# power-supply.net
KiCad netlist of a schematic drawn in EAGLE
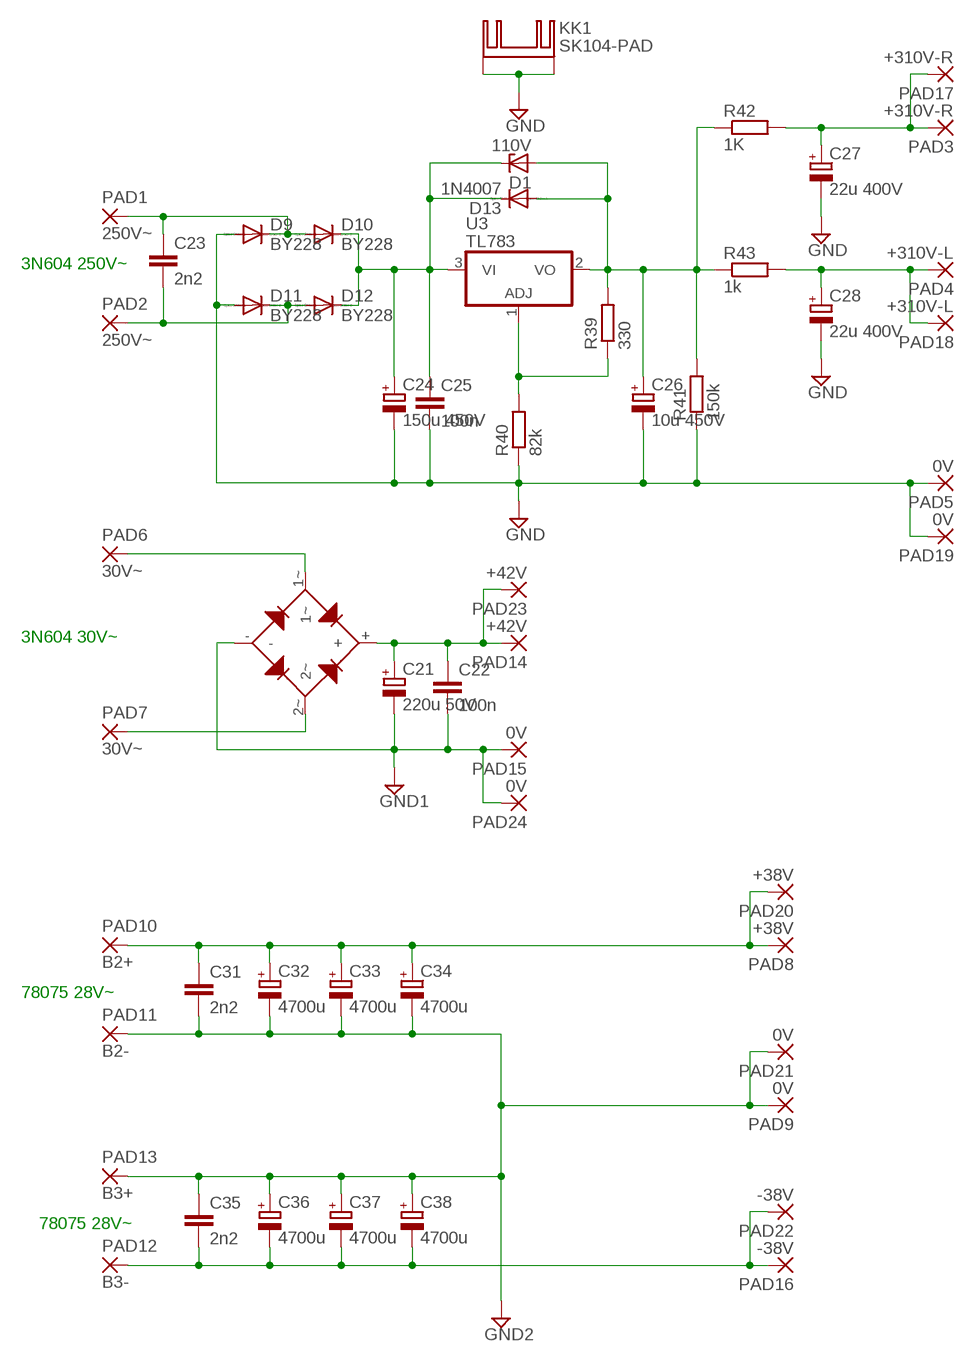
[diagram p0: schematic, sheet 1]

(export (version "E")
  (design (tool "Eeschema 10.0.6"))
  (components
    (comp (ref "C21")
      (value "220u 50V")
      (footprint "eagle-import:E5-10,5")
      (libsource (lib "eagle-import") (part "CPOL-EUE5-10.5"))
    )
    (comp (ref "C22")
      (value "100n")
      (footprint "eagle-import:C050-025X075")
      (libsource (lib "eagle-import") (part "C-EU050-025X075"))
    )
    (comp (ref "C23")
      (value "2n2")
      (footprint "eagle-import:C225-087X268")
      (libsource (lib "eagle-import") (part "C-EU225-087X268"))
    )
    (comp (ref "C24")
      (value "150u 450V")
      (footprint "eagle-import:E7,5-18")
      (libsource (lib "eagle-import") (part "CPOL-EUE7.5-18"))
    )
    (comp (ref "C25")
      (value "100n")
      (footprint "eagle-import:C150-054X183")
      (libsource (lib "eagle-import") (part "C-EU150-054X183"))
    )
    (comp (ref "C26")
      (value "10u 450V")
      (footprint "eagle-import:E7,5-16")
      (libsource (lib "eagle-import") (part "CPOL-EUE7.5-16"))
    )
    (comp (ref "C27")
      (value "22u 400V")
      (footprint "eagle-import:E5-13")
      (libsource (lib "eagle-import") (part "CPOL-EUE5-13"))
    )
    (comp (ref "C28")
      (value "22u 400V")
      (footprint "eagle-import:E5-13")
      (libsource (lib "eagle-import") (part "CPOL-EUE5-13"))
    )
    (comp (ref "C31")
      (value "2n2")
      (footprint "eagle-import:C225-087X268")
      (libsource (lib "eagle-import") (part "C-EU225-087X268"))
    )
    (comp (ref "C32")
      (value "4700u")
      (footprint "eagle-import:EB35D")
      (libsource (lib "eagle-import") (part "CPOL-EUE10-35"))
    )
    (comp (ref "C33")
      (value "4700u")
      (footprint "eagle-import:EB35D")
      (libsource (lib "eagle-import") (part "CPOL-EUE10-35"))
    )
    (comp (ref "C34")
      (value "4700u")
      (footprint "eagle-import:EB35D")
      (libsource (lib "eagle-import") (part "CPOL-EUE10-35"))
    )
    (comp (ref "C35")
      (value "2n2")
      (footprint "eagle-import:C225-087X268")
      (libsource (lib "eagle-import") (part "C-EU225-087X268"))
    )
    (comp (ref "C36")
      (value "4700u")
      (footprint "eagle-import:EB35D")
      (libsource (lib "eagle-import") (part "CPOL-EUE10-35"))
    )
    (comp (ref "C37")
      (value "4700u")
      (footprint "eagle-import:EB35D")
      (libsource (lib "eagle-import") (part "CPOL-EUE10-35"))
    )
    (comp (ref "C38")
      (value "4700u")
      (footprint "eagle-import:EB35D")
      (libsource (lib "eagle-import") (part "CPOL-EUE10-35"))
    )
    (comp (ref "D1")
      (value "110V")
      (footprint "eagle-import:F126Z10")
      (libsource (lib "eagle-import") (part "ZENER-DIODEF126-10"))
    )
    (comp (ref "D9")
      (value "BY228")
      (footprint "eagle-import:SOD64-10")
      (libsource (lib "eagle-import") (part "BY228"))
    )
    (comp (ref "D10")
      (value "BY228")
      (footprint "eagle-import:SOD64-10")
      (libsource (lib "eagle-import") (part "BY228"))
    )
    (comp (ref "D11")
      (value "BY228")
      (footprint "eagle-import:SOD64-10")
      (libsource (lib "eagle-import") (part "BY228"))
    )
    (comp (ref "D12")
      (value "BY228")
      (footprint "eagle-import:SOD64-10")
      (libsource (lib "eagle-import") (part "BY228"))
    )
    (comp (ref "D13")
      (value "1N4007")
      (footprint "eagle-import:DO41-10")
      (fields (field (name "SPICEPREFIX") "D"))
      (libsource (lib "eagle-import") (part "1N4004"))
    )
    (comp (ref "KK1")
      (value "SK104-PAD")
      (footprint "eagle-import:SK104-PAD")
      (libsource (lib "eagle-import") (part "SK104-PAD"))
    )
    (comp (ref "PAD1")
      (value "250V~")
      (footprint "eagle-import:3,81_1,4")
      (libsource (lib "eagle-import") (part "WIREPAD3,81/1,4"))
    )
    (comp (ref "PAD2")
      (value "250V~")
      (footprint "eagle-import:3,81_1,4")
      (libsource (lib "eagle-import") (part "WIREPAD3,81/1,4"))
    )
    (comp (ref "PAD3")
      (value "+310V-R")
      (footprint "eagle-import:3,81_1,4")
      (libsource (lib "eagle-import") (part "WIREPAD3,81/1,4"))
    )
    (comp (ref "PAD4")
      (value "+310V-L")
      (footprint "eagle-import:3,81_1,4")
      (libsource (lib "eagle-import") (part "WIREPAD3,81/1,4"))
    )
    (comp (ref "PAD5")
      (value "0V")
      (footprint "eagle-import:3,81_1,4")
      (libsource (lib "eagle-import") (part "WIREPAD3,81/1,4"))
    )
    (comp (ref "PAD6")
      (value "30V~")
      (footprint "eagle-import:3,81_1,4")
      (libsource (lib "eagle-import") (part "WIREPAD3,81/1,4"))
    )
    (comp (ref "PAD7")
      (value "30V~")
      (footprint "eagle-import:3,81_1,4")
      (libsource (lib "eagle-import") (part "WIREPAD3,81/1,4"))
    )
    (comp (ref "PAD8")
      (value "+38V")
      (footprint "eagle-import:3,81_1,4")
      (libsource (lib "eagle-import") (part "WIREPAD3,81/1,4"))
    )
    (comp (ref "PAD9")
      (value "0V")
      (footprint "eagle-import:3,81_1,4")
      (libsource (lib "eagle-import") (part "WIREPAD3,81/1,4"))
    )
    (comp (ref "PAD10")
      (value "B2+")
      (footprint "eagle-import:3,81_1,4")
      (libsource (lib "eagle-import") (part "WIREPAD3,81/1,4"))
    )
    (comp (ref "PAD11")
      (value "B2-")
      (footprint "eagle-import:3,81_1,4")
      (libsource (lib "eagle-import") (part "WIREPAD3,81/1,4"))
    )
    (comp (ref "PAD12")
      (value "B3-")
      (footprint "eagle-import:3,81_1,4")
      (libsource (lib "eagle-import") (part "WIREPAD3,81/1,4"))
    )
    (comp (ref "PAD13")
      (value "B3+")
      (footprint "eagle-import:3,81_1,4")
      (libsource (lib "eagle-import") (part "WIREPAD3,81/1,4"))
    )
    (comp (ref "PAD14")
      (value "+42V")
      (footprint "eagle-import:3,81_1,4")
      (libsource (lib "eagle-import") (part "WIREPAD3,81/1,4"))
    )
    (comp (ref "PAD15")
      (value "0V")
      (footprint "eagle-import:3,81_1,4")
      (libsource (lib "eagle-import") (part "WIREPAD3,81/1,4"))
    )
    (comp (ref "PAD16")
      (value "-38V")
      (footprint "eagle-import:3,81_1,4")
      (libsource (lib "eagle-import") (part "WIREPAD3,81/1,4"))
    )
    (comp (ref "PAD17")
      (value "+310V-R")
      (footprint "eagle-import:3,81_1,4")
      (libsource (lib "eagle-import") (part "WIREPAD3,81/1,4"))
    )
    (comp (ref "PAD18")
      (value "+310V-L")
      (footprint "eagle-import:3,81_1,4")
      (libsource (lib "eagle-import") (part "WIREPAD3,81/1,4"))
    )
    (comp (ref "PAD19")
      (value "0V")
      (footprint "eagle-import:3,81_1,4")
      (libsource (lib "eagle-import") (part "WIREPAD3,81/1,4"))
    )
    (comp (ref "PAD20")
      (value "+38V")
      (footprint "eagle-import:3,81_1,4")
      (libsource (lib "eagle-import") (part "WIREPAD3,81/1,4"))
    )
    (comp (ref "PAD21")
      (value "0V")
      (footprint "eagle-import:3,81_1,4")
      (libsource (lib "eagle-import") (part "WIREPAD3,81/1,4"))
    )
    (comp (ref "PAD22")
      (value "-38V")
      (footprint "eagle-import:3,81_1,4")
      (libsource (lib "eagle-import") (part "WIREPAD3,81/1,4"))
    )
    (comp (ref "PAD23")
      (value "+42V")
      (footprint "eagle-import:3,81_1,4")
      (libsource (lib "eagle-import") (part "WIREPAD3,81/1,4"))
    )
    (comp (ref "PAD24")
      (value "0V")
      (footprint "eagle-import:3,81_1,4")
      (libsource (lib "eagle-import") (part "WIREPAD3,81/1,4"))
    )
    (comp (ref "R39")
      (value "330")
      (footprint "eagle-import:0207_7")
      (libsource (lib "eagle-import") (part "R-EU_0207/7"))
    )
    (comp (ref "R40")
      (value "82k")
      (footprint "eagle-import:0617_22")
      (libsource (lib "eagle-import") (part "R-EU_0617/22"))
    )
    (comp (ref "R41")
      (value "150k")
      (footprint "eagle-import:0617_22")
      (libsource (lib "eagle-import") (part "R-EU_0617/22"))
    )
    (comp (ref "R42")
      (value "1K")
      (footprint "eagle-import:0309_12")
      (libsource (lib "eagle-import") (part "R-EU_0309/12"))
    )
    (comp (ref "R43")
      (value "1k")
      (footprint "eagle-import:0309_12")
      (libsource (lib "eagle-import") (part "R-EU_0309/12"))
    )
    (comp (ref "U$1")
      (value "W10G")
      (footprint "eagle-import:WOG")
      (libsource (lib "eagle-import") (part "W10G"))
    )
    (comp (ref "U3")
      (value "TL783")
      (footprint "eagle-import:TO220V")
      (libsource (lib "eagle-import") (part "MC33269?T"))
    )
  )
  (nets
    (net (code "1") (name "GND") (class "Default")
      (node (ref "C24") (pin "-") (pinfunction "-_-") (pintype "passive"))
      (node (ref "C25") (pin "2") (pinfunction "2_2") (pintype "passive"))
      (node (ref "C26") (pin "-") (pinfunction "-_-") (pintype "passive"))
      (node (ref "C27") (pin "-") (pinfunction "-_-") (pintype "passive"))
      (node (ref "C28") (pin "-") (pinfunction "-_-") (pintype "passive"))
      (node (ref "D11") (pin "A") (pinfunction "A_A") (pintype "passive"))
      (node (ref "D9") (pin "A") (pinfunction "A_A") (pintype "passive"))
      (node (ref "KK1") (pin "K1") (pinfunction "K_K1") (pintype "passive"))
      (node (ref "KK1") (pin "K2") (pinfunction "K_K2") (pintype "passive"))
      (node (ref "PAD19") (pin "1") (pinfunction "P_1") (pintype "passive"))
      (node (ref "PAD5") (pin "1") (pinfunction "P_1") (pintype "passive"))
      (node (ref "R40") (pin "1") (pinfunction "1_1") (pintype "passive"))
      (node (ref "R41") (pin "1") (pinfunction "1_1") (pintype "passive"))
    )
    (net (code "2") (name "GND1") (class "Default")
      (node (ref "C21") (pin "-") (pinfunction "-_-") (pintype "passive"))
      (node (ref "C22") (pin "2") (pinfunction "2_2") (pintype "passive"))
      (node (ref "PAD15") (pin "1") (pinfunction "P_1") (pintype "passive"))
      (node (ref "PAD24") (pin "1") (pinfunction "P_1") (pintype "passive"))
      (node (ref "U$1") (pin "-") (pinfunction "-_-") (pintype "bidirectional"))
    )
    (net (code "3") (name "GND2") (class "Default")
      (node (ref "C31") (pin "2") (pinfunction "2_2") (pintype "passive"))
      (node (ref "C32") (pin "-") (pinfunction "-_-") (pintype "passive"))
      (node (ref "C33") (pin "-") (pinfunction "-_-") (pintype "passive"))
      (node (ref "C34") (pin "-") (pinfunction "-_-") (pintype "passive"))
      (node (ref "C35") (pin "1") (pinfunction "1_1") (pintype "passive"))
      (node (ref "C36") (pin "+") (pinfunction "+_+") (pintype "passive"))
      (node (ref "C37") (pin "+") (pinfunction "+_+") (pintype "passive"))
      (node (ref "C38") (pin "+") (pinfunction "+_+") (pintype "passive"))
      (node (ref "PAD11") (pin "1") (pinfunction "P_1") (pintype "passive"))
      (node (ref "PAD13") (pin "1") (pinfunction "P_1") (pintype "passive"))
      (node (ref "PAD21") (pin "1") (pinfunction "P_1") (pintype "passive"))
      (node (ref "PAD9") (pin "1") (pinfunction "P_1") (pintype "passive"))
    )
    (net (code "4") (name "Net-(PAD1-P)") (class "Default")
      (node (ref "C23") (pin "1") (pinfunction "1_1") (pintype "passive"))
      (node (ref "D10") (pin "A") (pinfunction "A_A") (pintype "passive"))
      (node (ref "D9") (pin "C") (pinfunction "C_C") (pintype "passive"))
      (node (ref "PAD1") (pin "1") (pinfunction "P_1") (pintype "passive"))
    )
    (net (code "5") (name "Net-(PAD2-P)") (class "Default")
      (node (ref "C23") (pin "2") (pinfunction "2_2") (pintype "passive"))
      (node (ref "D11") (pin "C") (pinfunction "C_C") (pintype "passive"))
      (node (ref "D12") (pin "A") (pinfunction "A_A") (pintype "passive"))
      (node (ref "PAD2") (pin "1") (pinfunction "P_1") (pintype "passive"))
    )
    (net (code "6") (name "Net-(PAD6-P)") (class "Default")
      (node (ref "PAD6") (pin "1") (pinfunction "P_1") (pintype "passive"))
      (node (ref "U$1") (pin "1~") (pinfunction "1~{}_1~") (pintype "bidirectional"))
    )
    (net (code "7") (name "Net-(PAD7-P)") (class "Default")
      (node (ref "PAD7") (pin "1") (pinfunction "P_1") (pintype "passive"))
      (node (ref "U$1") (pin "2~") (pinfunction "2~{}_2~") (pintype "bidirectional"))
    )
    (net (code "8") (name "Net-(PAD10-P)") (class "Default")
      (node (ref "C31") (pin "1") (pinfunction "1_1") (pintype "passive"))
      (node (ref "C32") (pin "+") (pinfunction "+_+") (pintype "passive"))
      (node (ref "C33") (pin "+") (pinfunction "+_+") (pintype "passive"))
      (node (ref "C34") (pin "+") (pinfunction "+_+") (pintype "passive"))
      (node (ref "PAD10") (pin "1") (pinfunction "P_1") (pintype "passive"))
      (node (ref "PAD20") (pin "1") (pinfunction "P_1") (pintype "passive"))
      (node (ref "PAD8") (pin "1") (pinfunction "P_1") (pintype "passive"))
    )
    (net (code "9") (name "Net-(PAD12-P)") (class "Default")
      (node (ref "C35") (pin "2") (pinfunction "2_2") (pintype "passive"))
      (node (ref "C36") (pin "-") (pinfunction "-_-") (pintype "passive"))
      (node (ref "C37") (pin "-") (pinfunction "-_-") (pintype "passive"))
      (node (ref "C38") (pin "-") (pinfunction "-_-") (pintype "passive"))
      (node (ref "PAD12") (pin "1") (pinfunction "P_1") (pintype "passive"))
      (node (ref "PAD16") (pin "1") (pinfunction "P_1") (pintype "passive"))
      (node (ref "PAD22") (pin "1") (pinfunction "P_1") (pintype "passive"))
    )
    (net (code "10") (name "Net-(PAD14-P)") (class "Default")
      (node (ref "C21") (pin "+") (pinfunction "+_+") (pintype "passive"))
      (node (ref "C22") (pin "1") (pinfunction "1_1") (pintype "passive"))
      (node (ref "PAD14") (pin "1") (pinfunction "P_1") (pintype "passive"))
      (node (ref "PAD23") (pin "1") (pinfunction "P_1") (pintype "passive"))
      (node (ref "U$1") (pin "+") (pinfunction "+_+") (pintype "bidirectional"))
    )
    (net (code "11") (name "Net-(PAD17-P)") (class "Default")
      (node (ref "C27") (pin "+") (pinfunction "+_+") (pintype "passive"))
      (node (ref "PAD17") (pin "1") (pinfunction "P_1") (pintype "passive"))
      (node (ref "PAD3") (pin "1") (pinfunction "P_1") (pintype "passive"))
      (node (ref "R42") (pin "2") (pinfunction "2_2") (pintype "passive"))
    )
    (net (code "12") (name "Net-(PAD18-P)") (class "Default")
      (node (ref "C28") (pin "+") (pinfunction "+_+") (pintype "passive"))
      (node (ref "PAD18") (pin "1") (pinfunction "P_1") (pintype "passive"))
      (node (ref "PAD4") (pin "1") (pinfunction "P_1") (pintype "passive"))
      (node (ref "R43") (pin "2") (pinfunction "2_2") (pintype "passive"))
    )
    (net (code "13") (name "Net-(U3-ADJ)") (class "Default")
      (node (ref "R39") (pin "1") (pinfunction "1_1") (pintype "passive"))
      (node (ref "R40") (pin "2") (pinfunction "2_2") (pintype "passive"))
      (node (ref "U3") (pin "1") (pinfunction "ADJ_1") (pintype "input"))
    )
    (net (code "14") (name "Net-(U3-VI)") (class "Default")
      (node (ref "C24") (pin "+") (pinfunction "+_+") (pintype "passive"))
      (node (ref "C25") (pin "1") (pinfunction "1_1") (pintype "passive"))
      (node (ref "D1") (pin "C") (pinfunction "C_C") (pintype "passive"))
      (node (ref "D10") (pin "C") (pinfunction "C_C") (pintype "passive"))
      (node (ref "D12") (pin "C") (pinfunction "C_C") (pintype "passive"))
      (node (ref "D13") (pin "C") (pinfunction "C_C") (pintype "passive"))
      (node (ref "U3") (pin "3") (pinfunction "VI_3") (pintype "input"))
    )
    (net (code "15") (name "Net-(U3-VO)") (class "Default")
      (node (ref "C26") (pin "+") (pinfunction "+_+") (pintype "passive"))
      (node (ref "D1") (pin "A") (pinfunction "A_A") (pintype "passive"))
      (node (ref "D13") (pin "A") (pinfunction "A_A") (pintype "passive"))
      (node (ref "R39") (pin "2") (pinfunction "2_2") (pintype "passive"))
      (node (ref "R41") (pin "2") (pinfunction "2_2") (pintype "passive"))
      (node (ref "R42") (pin "1") (pinfunction "1_1") (pintype "passive"))
      (node (ref "R43") (pin "1") (pinfunction "1_1") (pintype "passive"))
      (node (ref "U3") (pin "2") (pinfunction "VO_2") (pintype "passive"))
    )
  )
)
